# Starboard_Deployable_Headers.net
KiCad netlist of a schematic drawn in Altium Designer
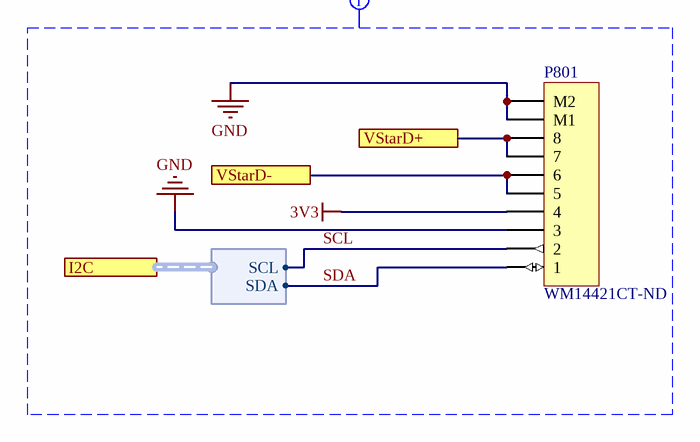
[diagram p0: Starboard_Deployable_Headers.SchDoc]

(export (version "E")
  (design (tool "Eeschema 10.0.6"))
  (components
    (comp (ref "P801")
      (value "WM14421CT-ND")
      (footprint "MOLX-5040500891")
      (description "CONN HEADER SMD R/A 8POS 1.5MM")
      (fields
        (field (name "PART NUMBER") "67")
        (field (name "MANUFACTURER PART NUMBER") "5040500891")
        (field (name "PUBLISHER") "Altium Limited")
      )
      (libsource (lib "Database") (part "Header 10"))
    )
  )
  (nets
    (net (code "2") (name "/SCL") (class "Default")
      (node (ref "P801") (pin "2") (pinfunction "2_2") (pintype "output"))
    )
    (net (code "3") (name "/SDA") (class "Default")
      (node (ref "P801") (pin "1") (pinfunction "1_1") (pintype "bidirectional"))
    )
    (net (code "4") (name "/VStarD+") (class "Default")
      (node (ref "P801") (pin "7") (pinfunction "7_7") (pintype "passive"))
      (node (ref "P801") (pin "8") (pinfunction "8_8") (pintype "passive"))
    )
    (net (code "5") (name "/VStarD-") (class "Default")
      (node (ref "P801") (pin "5") (pinfunction "5_5") (pintype "passive"))
      (node (ref "P801") (pin "6") (pinfunction "6_6") (pintype "passive"))
    )
    (net (code "7") (name "3V3") (class "Default")
      (node (ref "P801") (pin "4") (pinfunction "4_4") (pintype "passive"))
    )
    (net (code "8") (name "GND") (class "Default")
      (node (ref "P801") (pin "3") (pinfunction "3_3") (pintype "passive"))
      (node (ref "P801") (pin "M1") (pinfunction "M1_M1") (pintype "passive"))
      (node (ref "P801") (pin "M2") (pinfunction "M2_M2") (pintype "passive"))
    )
  )
)
